# Main.net
KiCad netlist of a schematic drawn in Altium Designer
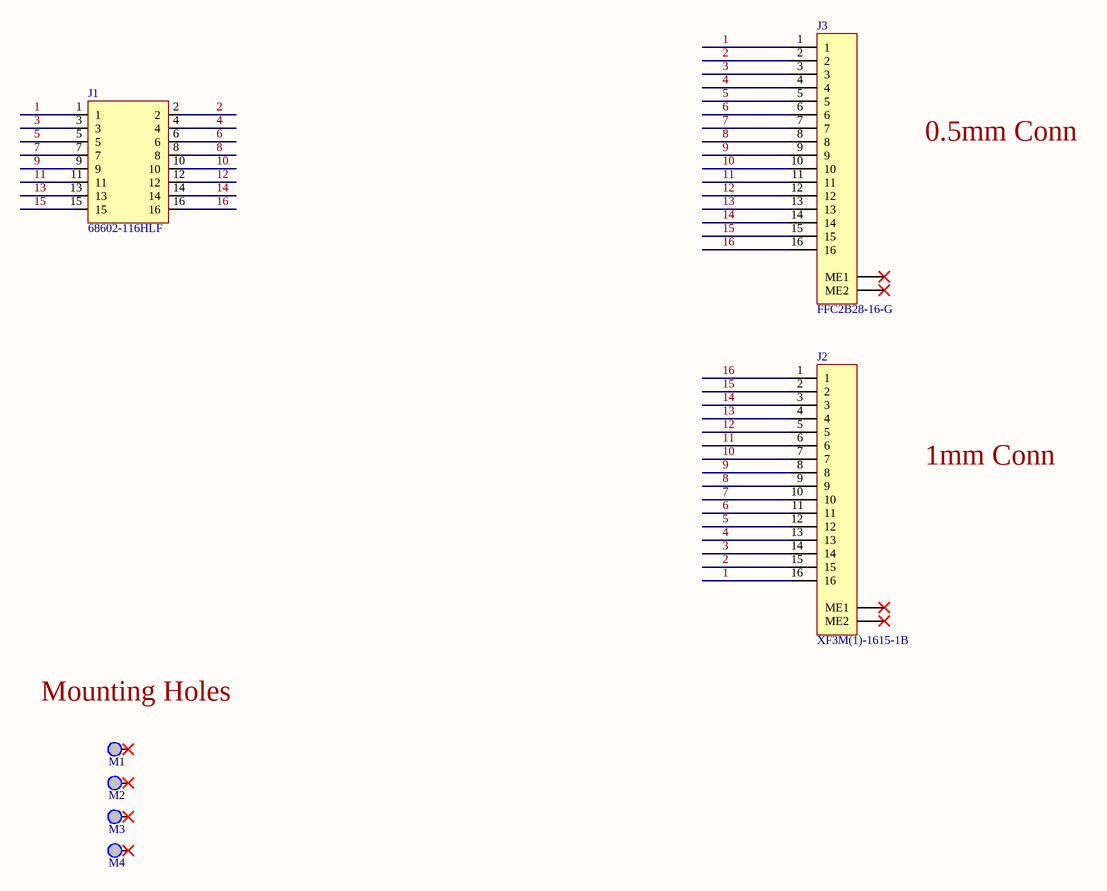
[diagram p0: Main.SchDoc]

(export (version "E")
  (design (tool "Eeschema 10.0.6"))
  (components
    (comp (ref "J1")
      (value "68602-116HLF")
      (footprint "HDR-V-2X8-2.54MM")
      (description "Conn Unshrouded Header HDR 16 POS 2.54mm Solder ST Top Entry Thru-Hole BergStik® Bulk")
      (libsource (lib "intercreate") (part "HDR-V-2X8-M-2.54MM"))
    )
    (comp (ref "J2")
      (value "XF3M(1)-1615-1B")
      (footprint "CONN-FFC-H-16P-1MM")
      (description "1.0-mm Pitch, Dual Contact ; For FPC/FFC, 16 Contacts, RoHS")
      (libsource (lib "intercreate") (part "CONN-FFC-H-16P-1MM"))
    )
    (comp (ref "J3")
      (value "FFC2B28-16-G")
      (footprint "CONN-FFC-H-16P-0.5MM")
      (libsource (lib "intercreate") (part "CONN-FFC-H-16P-0.5MM"))
    )
    (comp (ref "M1")
      (value "MTG_HOLE")
      (footprint "MH_P_2.5MM")
      (description "MTG HOLE PLATED VARIOUS SIZES")
      (libsource (lib "intercreate") (part "MTG_HOLE"))
    )
    (comp (ref "M2")
      (value "MTG_HOLE")
      (footprint "MH_P_2.5MM")
      (description "MTG HOLE PLATED VARIOUS SIZES")
      (libsource (lib "intercreate") (part "MTG_HOLE"))
    )
    (comp (ref "M3")
      (value "MTG_HOLE")
      (footprint "MH_P_2.5MM")
      (description "MTG HOLE PLATED VARIOUS SIZES")
      (libsource (lib "intercreate") (part "MTG_HOLE"))
    )
    (comp (ref "M4")
      (value "MTG_HOLE")
      (footprint "MH_P_2.5MM")
      (description "MTG HOLE PLATED VARIOUS SIZES")
      (libsource (lib "intercreate") (part "MTG_HOLE"))
    )
  )
  (nets
    (net (code "1") (name "/1") (class "Default")
      (node (ref "J1") (pin "1") (pinfunction "1_1") (pintype "passive"))
      (node (ref "J2") (pin "16") (pinfunction "16_16") (pintype "passive"))
      (node (ref "J3") (pin "1") (pinfunction "1_1") (pintype "passive"))
    )
    (net (code "2") (name "/2") (class "Default")
      (node (ref "J1") (pin "2") (pinfunction "2_2") (pintype "passive"))
      (node (ref "J2") (pin "15") (pinfunction "15_15") (pintype "passive"))
      (node (ref "J3") (pin "2") (pinfunction "2_2") (pintype "passive"))
    )
    (net (code "3") (name "/3") (class "Default")
      (node (ref "J1") (pin "3") (pinfunction "3_3") (pintype "passive"))
      (node (ref "J2") (pin "14") (pinfunction "14_14") (pintype "passive"))
      (node (ref "J3") (pin "3") (pinfunction "3_3") (pintype "passive"))
    )
    (net (code "4") (name "/4") (class "Default")
      (node (ref "J1") (pin "4") (pinfunction "4_4") (pintype "passive"))
      (node (ref "J2") (pin "13") (pinfunction "13_13") (pintype "passive"))
      (node (ref "J3") (pin "4") (pinfunction "4_4") (pintype "passive"))
    )
    (net (code "5") (name "/5") (class "Default")
      (node (ref "J1") (pin "5") (pinfunction "5_5") (pintype "passive"))
      (node (ref "J2") (pin "12") (pinfunction "12_12") (pintype "passive"))
      (node (ref "J3") (pin "5") (pinfunction "5_5") (pintype "passive"))
    )
    (net (code "6") (name "/6") (class "Default")
      (node (ref "J1") (pin "6") (pinfunction "6_6") (pintype "passive"))
      (node (ref "J2") (pin "11") (pinfunction "11_11") (pintype "passive"))
      (node (ref "J3") (pin "6") (pinfunction "6_6") (pintype "passive"))
    )
    (net (code "7") (name "/7") (class "Default")
      (node (ref "J1") (pin "7") (pinfunction "7_7") (pintype "passive"))
      (node (ref "J2") (pin "10") (pinfunction "10_10") (pintype "passive"))
      (node (ref "J3") (pin "7") (pinfunction "7_7") (pintype "passive"))
    )
    (net (code "8") (name "/8") (class "Default")
      (node (ref "J1") (pin "8") (pinfunction "8_8") (pintype "passive"))
      (node (ref "J2") (pin "9") (pinfunction "9_9") (pintype "passive"))
      (node (ref "J3") (pin "8") (pinfunction "8_8") (pintype "passive"))
    )
    (net (code "9") (name "/9") (class "Default")
      (node (ref "J1") (pin "9") (pinfunction "9_9") (pintype "passive"))
      (node (ref "J2") (pin "8") (pinfunction "8_8") (pintype "passive"))
      (node (ref "J3") (pin "9") (pinfunction "9_9") (pintype "passive"))
    )
    (net (code "10") (name "/10") (class "Default")
      (node (ref "J1") (pin "10") (pinfunction "10_10") (pintype "passive"))
      (node (ref "J2") (pin "7") (pinfunction "7_7") (pintype "passive"))
      (node (ref "J3") (pin "10") (pinfunction "10_10") (pintype "passive"))
    )
    (net (code "11") (name "/11") (class "Default")
      (node (ref "J1") (pin "11") (pinfunction "11_11") (pintype "passive"))
      (node (ref "J2") (pin "6") (pinfunction "6_6") (pintype "passive"))
      (node (ref "J3") (pin "11") (pinfunction "11_11") (pintype "passive"))
    )
    (net (code "12") (name "/12") (class "Default")
      (node (ref "J1") (pin "12") (pinfunction "12_12") (pintype "passive"))
      (node (ref "J2") (pin "5") (pinfunction "5_5") (pintype "passive"))
      (node (ref "J3") (pin "12") (pinfunction "12_12") (pintype "passive"))
    )
    (net (code "13") (name "/13") (class "Default")
      (node (ref "J1") (pin "13") (pinfunction "13_13") (pintype "passive"))
      (node (ref "J2") (pin "4") (pinfunction "4_4") (pintype "passive"))
      (node (ref "J3") (pin "13") (pinfunction "13_13") (pintype "passive"))
    )
    (net (code "14") (name "/14") (class "Default")
      (node (ref "J1") (pin "14") (pinfunction "14_14") (pintype "passive"))
      (node (ref "J2") (pin "3") (pinfunction "3_3") (pintype "passive"))
      (node (ref "J3") (pin "14") (pinfunction "14_14") (pintype "passive"))
    )
    (net (code "15") (name "/15") (class "Default")
      (node (ref "J1") (pin "15") (pinfunction "15_15") (pintype "passive"))
      (node (ref "J2") (pin "2") (pinfunction "2_2") (pintype "passive"))
      (node (ref "J3") (pin "15") (pinfunction "15_15") (pintype "passive"))
    )
    (net (code "16") (name "/16") (class "Default")
      (node (ref "J1") (pin "16") (pinfunction "16_16") (pintype "passive"))
      (node (ref "J2") (pin "1") (pinfunction "1_1") (pintype "passive"))
      (node (ref "J3") (pin "16") (pinfunction "16_16") (pintype "passive"))
    )
    (net (code "17") (name "unconnected-(J2-PadME1)") (class "Default")
      (node (ref "J2") (pin "ME1") (pinfunction "ME1_ME1") (pintype "passive+no_connect"))
    )
    (net (code "18") (name "unconnected-(J2-PadME2)") (class "Default")
      (node (ref "J2") (pin "ME2") (pinfunction "ME2_ME2") (pintype "passive+no_connect"))
    )
    (net (code "19") (name "unconnected-(J3-PadME1)") (class "Default")
      (node (ref "J3") (pin "ME1") (pinfunction "ME1_ME1") (pintype "passive+no_connect"))
    )
    (net (code "20") (name "unconnected-(J3-PadME2)") (class "Default")
      (node (ref "J3") (pin "ME2") (pinfunction "ME2_ME2") (pintype "passive+no_connect"))
    )
    (net (code "21") (name "unconnected-(M1-Pad1)") (class "Default")
      (node (ref "M1") (pin "1") (pinfunction "1_1") (pintype "passive+no_connect"))
    )
    (net (code "22") (name "unconnected-(M2-Pad1)") (class "Default")
      (node (ref "M2") (pin "1") (pinfunction "1_1") (pintype "passive+no_connect"))
    )
    (net (code "23") (name "unconnected-(M3-Pad1)") (class "Default")
      (node (ref "M3") (pin "1") (pinfunction "1_1") (pintype "passive+no_connect"))
    )
    (net (code "24") (name "unconnected-(M4-Pad1)") (class "Default")
      (node (ref "M4") (pin "1") (pinfunction "1_1") (pintype "passive+no_connect"))
    )
  )
)
